# 05_DATA_IO.net
KiCad netlist of a schematic drawn in Altium Designer
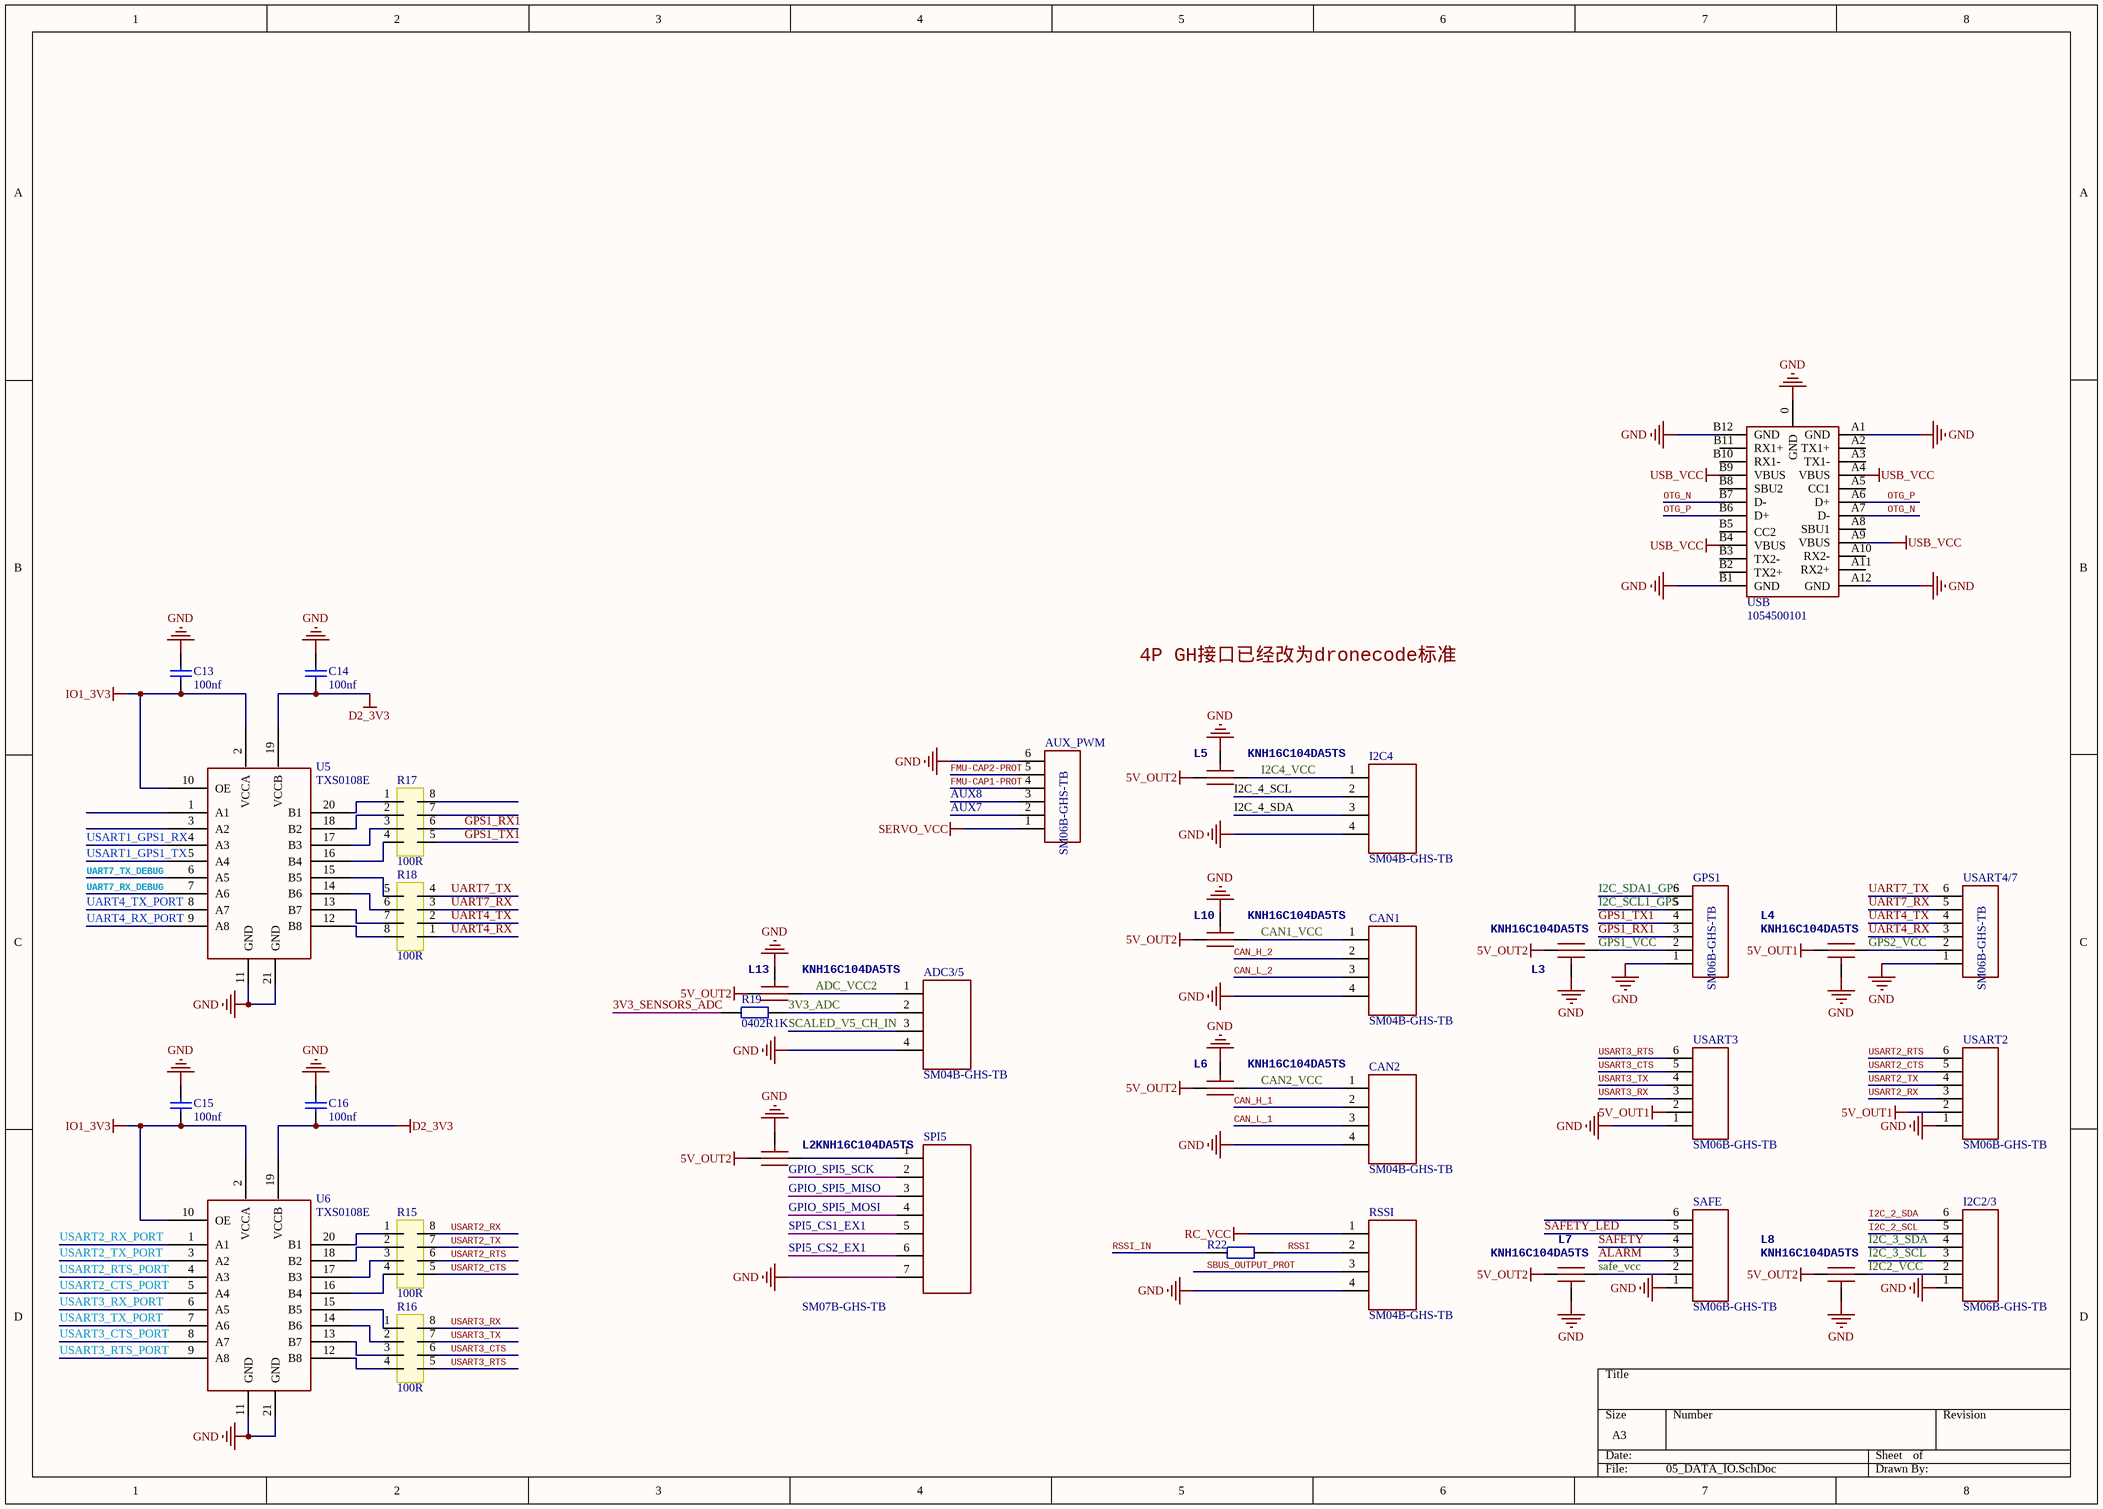
[diagram p0: 05_DATA_IO.SchDoc]

(export (version "E")
  (design (tool "Eeschema 10.0.6"))
  (components
    (comp (ref "ADC3/5")
      (value "SM04B-GHS-TB")
      (footprint "BM04B-GHS_DC")
      (libsource (lib "CUAV") (part "SM04B-GHS-TB"))
    )
    (comp (ref "AUX_PWM")
      (value "SM06B-GHS-TB")
      (footprint "BM06B-GHS_DC")
      (description "dronecode")
      (libsource (lib "CUAV") (part "SM06B-GHS-TB"))
    )
    (comp (ref "C13") (value "100nf") (libsource (lib "Miscellaneous Devices") (part "Cap")))
    (comp (ref "C14") (value "100nf") (libsource (lib "Miscellaneous Devices") (part "Cap")))
    (comp (ref "C15") (value "100nf") (libsource (lib "Miscellaneous Devices") (part "Cap")))
    (comp (ref "C16") (value "100nf") (libsource (lib "Miscellaneous Devices") (part "Cap")))
    (comp (ref "CAN1")
      (value "SM04B-GHS-TB")
      (footprint "BM04B-GHS_DC")
      (description "dronecode")
      (libsource (lib "CUAV") (part "SM04B-GHS-TB"))
    )
    (comp (ref "CAN2")
      (value "SM04B-GHS-TB")
      (footprint "BM04B-GHS_DC")
      (description "dronecode")
      (libsource (lib "CUAV") (part "SM04B-GHS-TB"))
    )
    (comp (ref "GPS1")
      (value "SM06B-GHS-TB")
      (footprint "SM06B-GHS-TB")
      (libsource (lib "CUAV") (part "SM06B-GHS-TB"))
    )
    (comp (ref "I2C2/3")
      (value "SM06B-GHS-TB")
      (footprint "SM06B-GHS-TB")
      (libsource (lib "CUAV") (part "SM06B-GHS-TB"))
    )
    (comp (ref "I2C4")
      (value "SM04B-GHS-TB")
      (footprint "BM04B-GHS_DC")
      (description "dronecode")
      (libsource (lib "CUAV") (part "SM04B-GHS-TB"))
    )
    (comp (ref "L2")
      (value "KNH16C104DA5TS")
      (footprint "KYOCERA-KNH16-DA")
      (description "Capacitor, Filter, 0.1uF, 25V, 2A, 0603, SMD")
      (fields (field (name "3DR_PARTNO") "ECM0719"))
      (libsource (lib "PCA_0005_FULL_CB_REV_A") (part "KNH16C104DA5TS"))
    )
    (comp (ref "L3")
      (value "KNH16C104DA5TS")
      (footprint "KYOCERA-KNH16-DA")
      (description "Capacitor, Filter, 0.1uF, 25V, 2A, 0603, SMD")
      (fields (field (name "3DR_PARTNO") "ECM0719"))
      (libsource (lib "PCA_0005_FULL_CB_REV_A") (part "KNH16C104DA5TS"))
    )
    (comp (ref "L4")
      (value "KNH16C104DA5TS")
      (footprint "KYOCERA-KNH16-DA")
      (description "Capacitor, Filter, 0.1uF, 25V, 2A, 0603, SMD")
      (fields (field (name "3DR_PARTNO") "ECM0719"))
      (libsource (lib "PCA_0005_FULL_CB_REV_A") (part "KNH16C104DA5TS"))
    )
    (comp (ref "L5")
      (value "KNH16C104DA5TS")
      (footprint "KYOCERA-KNH16-DA")
      (description "Capacitor, Filter, 0.1uF, 25V, 2A, 0603, SMD")
      (fields (field (name "3DR_PARTNO") "ECM0719"))
      (libsource (lib "PCA_0005_FULL_CB_REV_A") (part "KNH16C104DA5TS"))
    )
    (comp (ref "L6")
      (value "KNH16C104DA5TS")
      (footprint "KYOCERA-KNH16-DA")
      (description "Capacitor, Filter, 0.1uF, 25V, 2A, 0603, SMD")
      (fields (field (name "3DR_PARTNO") "ECM0719"))
      (libsource (lib "PCA_0005_FULL_CB_REV_A") (part "KNH16C104DA5TS"))
    )
    (comp (ref "L7")
      (value "KNH16C104DA5TS")
      (footprint "KYOCERA-KNH16-DA")
      (description "Capacitor, Filter, 0.1uF, 25V, 2A, 0603, SMD")
      (fields (field (name "3DR_PARTNO") "ECM0719"))
      (libsource (lib "PCA_0005_FULL_CB_REV_A") (part "KNH16C104DA5TS"))
    )
    (comp (ref "L8")
      (value "KNH16C104DA5TS")
      (footprint "KYOCERA-KNH16-DA")
      (description "Capacitor, Filter, 0.1uF, 25V, 2A, 0603, SMD")
      (fields (field (name "3DR_PARTNO") "ECM0719"))
      (libsource (lib "PCA_0005_FULL_CB_REV_A") (part "KNH16C104DA5TS"))
    )
    (comp (ref "L10")
      (value "KNH16C104DA5TS")
      (footprint "KYOCERA-KNH16-DA")
      (description "Capacitor, Filter, 0.1uF, 25V, 2A, 0603, SMD")
      (fields (field (name "3DR_PARTNO") "ECM0719"))
      (libsource (lib "PCA_0005_FULL_CB_REV_A") (part "KNH16C104DA5TS"))
    )
    (comp (ref "L13")
      (value "KNH16C104DA5TS")
      (footprint "KYOCERA-KNH16-DA")
      (description "Capacitor, Filter, 0.1uF, 25V, 2A, 0603, SMD")
      (fields (field (name "3DR_PARTNO") "ECM0719"))
      (libsource (lib "PCA_0005_FULL_CB_REV_A") (part "KNH16C104DA5TS"))
    )
    (comp (ref "R15") (value "100R") (footprint "0402_4r") (libsource (lib "") (part "0402-8R-4R_1")))
    (comp (ref "R16") (value "100R") (footprint "0402_4r") (libsource (lib "") (part "0402-8R-4R_1")))
    (comp (ref "R17") (value "100R") (footprint "0402_4r") (libsource (lib "") (part "0402-8R-4R_1")))
    (comp (ref "R18") (value "100R") (footprint "0402_4r") (libsource (lib "CUAV") (part "0402-8R-4R")))
    (comp (ref "R19")
      (value "0402R1K")
      (footprint "0402R")
      (description "0402R1K 1%")
      (libsource (lib "CUAV") (part "0402R1K"))
    )
    (comp (ref "R22")
      (value "0402R100R")
      (footprint "0402R")
      (description "0402R100R 1%")
      (libsource (lib "CUAV") (part "0402R100R"))
    )
    (comp (ref "RSSI")
      (value "SM04B-GHS-TB")
      (footprint "BM04B-GHS_DC")
      (description "dronecode")
      (libsource (lib "CUAV") (part "SM04B-GHS-TB"))
    )
    (comp (ref "SAFE")
      (value "SM06B-GHS-TB")
      (footprint "SM06B-GHS-TB")
      (libsource (lib "CUAV") (part "SM06B-GHS-TB"))
    )
    (comp (ref "SPI5")
      (value "SM07B-GHS-TB")
      (footprint "SM07B-GHS")
      (libsource (lib "CUAV") (part "SM07B-GHS-TB"))
    )
    (comp (ref "U5") (value "TXS0108E") (footprint "VQFN20") (libsource (lib "CUAV") (part "TXS0108E")))
    (comp (ref "U6") (value "TXS0108E") (footprint "VQFN20") (libsource (lib "CUAV") (part "TXS0108E")))
    (comp (ref "USART2")
      (value "SM06B-GHS-TB")
      (footprint "SM06B-GHS-TB")
      (libsource (lib "CUAV") (part "SM06B-GHS-TB"))
    )
    (comp (ref "USART3")
      (value "SM06B-GHS-TB")
      (footprint "SM06B-GHS-TB")
      (libsource (lib "CUAV") (part "SM06B-GHS-TB"))
    )
    (comp (ref "USART4/7")
      (value "SM06B-GHS-TB")
      (footprint "SM06B-GHS-TB")
      (libsource (lib "CUAV") (part "SM06B-GHS-TB"))
    )
    (comp (ref "USB")
      (value "1054500101")
      (footprint "1054500101")
      (libsource (lib "CUAV") (part "1054500101"))
    )
  )
  (nets
    (net (code "1") (name "/3V3_ADC") (class "Default")
      (node (ref "ADC3/5") (pin "2") (pintype "passive"))
      (node (ref "R19") (pin "2") (pintype "passive"))
    )
    (net (code "2") (name "/3V3_SENSORS_ADC") (class "Default")
      (node (ref "R19") (pin "1") (pintype "passive"))
    )
    (net (code "4") (name "/ADC_VCC2") (class "Default")
      (node (ref "ADC3/5") (pin "1") (pintype "passive"))
      (node (ref "L13") (pin "P$1") (pinfunction "P$1_P$1") (pintype "passive"))
    )
    (net (code "5") (name "/ALARM") (class "Default") (node (ref "SAFE") (pin "3") (pintype "passive")))
    (net (code "6") (name "/AUX7") (class "Default") (node (ref "AUX_PWM") (pin "2") (pintype "passive")))
    (net (code "7") (name "/AUX8") (class "Default") (node (ref "AUX_PWM") (pin "3") (pintype "passive")))
    (net (code "8") (name "/CAN1_VCC") (class "Default")
      (node (ref "CAN1") (pin "1") (pintype "passive"))
      (node (ref "L10") (pin "P$1") (pinfunction "P$1_P$1") (pintype "passive"))
    )
    (net (code "9") (name "/CAN2_VCC") (class "Default")
      (node (ref "CAN2") (pin "1") (pintype "passive"))
      (node (ref "L6") (pin "P$1") (pinfunction "P$1_P$1") (pintype "passive"))
    )
    (net (code "10") (name "/CAN_H_1") (class "Default") (node (ref "CAN2") (pin "2") (pintype "passive")))
    (net (code "11") (name "/CAN_H_2") (class "Default") (node (ref "CAN1") (pin "2") (pintype "passive")))
    (net (code "12") (name "/CAN_L_1") (class "Default") (node (ref "CAN2") (pin "3") (pintype "passive")))
    (net (code "13") (name "/CAN_L_2") (class "Default") (node (ref "CAN1") (pin "3") (pintype "passive")))
    (net (code "14") (name "/FMU-CAP1-PROT") (class "Default")
      (node (ref "AUX_PWM") (pin "4") (pintype "passive"))
    )
    (net (code "15") (name "/FMU-CAP2-PROT") (class "Default")
      (node (ref "AUX_PWM") (pin "5") (pintype "passive"))
    )
    (net (code "16") (name "/GPIO_SPI5_MISO") (class "Default")
      (node (ref "SPI5") (pin "3") (pintype "passive"))
    )
    (net (code "17") (name "/GPIO_SPI5_MOSI") (class "Default")
      (node (ref "SPI5") (pin "4") (pintype "passive"))
    )
    (net (code "18") (name "/GPIO_SPI5_SCK") (class "Default")
      (node (ref "SPI5") (pin "2") (pintype "passive"))
    )
    (net (code "19") (name "/GPS1_RX1") (class "Default")
      (node (ref "GPS1") (pin "3") (pintype "passive"))
      (node (ref "R17") (pin "6") (pinfunction "6_6") (pintype "passive"))
    )
    (net (code "20") (name "/GPS1_TX1") (class "Default")
      (node (ref "GPS1") (pin "4") (pintype "passive"))
      (node (ref "R17") (pin "5") (pinfunction "5_5") (pintype "passive"))
    )
    (net (code "21") (name "/GPS1_VCC") (class "Default")
      (node (ref "GPS1") (pin "2") (pintype "passive"))
      (node (ref "L3") (pin "P$2") (pinfunction "P$2_P$2") (pintype "passive"))
    )
    (net (code "22") (name "/GPS2_VCC") (class "Default")
      (node (ref "L4") (pin "P$2") (pinfunction "P$2_P$2") (pintype "passive"))
      (node (ref "USART4/7") (pin "2") (pintype "passive"))
    )
    (net (code "23") (name "/I2C2_VCC") (class "Default")
      (node (ref "I2C2/3") (pin "2") (pintype "passive"))
      (node (ref "L8") (pin "P$2") (pinfunction "P$2_P$2") (pintype "passive"))
    )
    (net (code "24") (name "/I2C4_VCC") (class "Default")
      (node (ref "I2C4") (pin "1") (pintype "passive"))
      (node (ref "L5") (pin "P$1") (pinfunction "P$1_P$1") (pintype "passive"))
    )
    (net (code "25") (name "/I2C_2_SCL") (class "Default")
      (node (ref "I2C2/3") (pin "5") (pintype "passive"))
    )
    (net (code "26") (name "/I2C_2_SDA") (class "Default")
      (node (ref "I2C2/3") (pin "6") (pintype "passive"))
    )
    (net (code "27") (name "/I2C_3_SCL") (class "Default")
      (node (ref "I2C2/3") (pin "3") (pintype "passive"))
    )
    (net (code "28") (name "/I2C_3_SDA") (class "Default")
      (node (ref "I2C2/3") (pin "4") (pintype "passive"))
    )
    (net (code "29") (name "/I2C_4_SCL") (class "Default") (node (ref "I2C4") (pin "2") (pintype "passive")))
    (net (code "30") (name "/I2C_4_SDA") (class "Default") (node (ref "I2C4") (pin "3") (pintype "passive")))
    (net (code "31") (name "/I2C_SCL1_GPS") (class "Default")
      (node (ref "GPS1") (pin "5") (pintype "passive"))
    )
    (net (code "32") (name "/I2C_SDA1_GPS") (class "Default")
      (node (ref "GPS1") (pin "6") (pintype "passive"))
    )
    (net (code "33") (name "/OTG_N") (class "Default")
      (node (ref "USB") (pin "A7") (pinfunction "D-_A7") (pintype "passive"))
      (node (ref "USB") (pin "B7") (pinfunction "D-_B7") (pintype "passive"))
    )
    (net (code "34") (name "/OTG_P") (class "Default")
      (node (ref "USB") (pin "A6") (pinfunction "D+_A6") (pintype "passive"))
      (node (ref "USB") (pin "B6") (pinfunction "D+_B6") (pintype "passive"))
    )
    (net (code "35") (name "/RSSI") (class "Default")
      (node (ref "R22") (pin "2") (pintype "passive"))
      (node (ref "RSSI") (pin "2") (pintype "passive"))
    )
    (net (code "36") (name "/RSSI_IN") (class "Default") (node (ref "R22") (pin "1") (pintype "passive")))
    (net (code "37") (name "/SAFETY") (class "Default") (node (ref "SAFE") (pin "4") (pintype "passive")))
    (net (code "38") (name "/SAFETY_LED") (class "Default") (node (ref "SAFE") (pin "5") (pintype "passive")))
    (net (code "39") (name "/SBUS_OUTPUT_PROT") (class "Default")
      (node (ref "RSSI") (pin "3") (pintype "passive"))
    )
    (net (code "40") (name "/SCALED_V5_CH_IN") (class "Default")
      (node (ref "ADC3/5") (pin "3") (pintype "passive"))
    )
    (net (code "41") (name "/SPI5_CS1_EX1") (class "Default")
      (node (ref "SPI5") (pin "5") (pintype "passive"))
    )
    (net (code "42") (name "/SPI5_CS2_EX1") (class "Default")
      (node (ref "SPI5") (pin "6") (pintype "passive"))
    )
    (net (code "43") (name "/UART4_RX") (class "Default")
      (node (ref "R18") (pin "1") (pinfunction "1_1") (pintype "passive"))
      (node (ref "USART4/7") (pin "3") (pintype "passive"))
    )
    (net (code "44") (name "/UART4_RX_PORT") (class "Default")
      (node (ref "U5") (pin "9") (pinfunction "A8_9") (pintype "passive"))
    )
    (net (code "45") (name "/UART4_TX") (class "Default")
      (node (ref "R18") (pin "2") (pinfunction "2_2") (pintype "passive"))
      (node (ref "USART4/7") (pin "4") (pintype "passive"))
    )
    (net (code "46") (name "/UART4_TX_PORT") (class "Default")
      (node (ref "U5") (pin "8") (pinfunction "A7_8") (pintype "passive"))
    )
    (net (code "47") (name "/UART7_RX") (class "Default")
      (node (ref "R18") (pin "3") (pinfunction "3_3") (pintype "passive"))
      (node (ref "USART4/7") (pin "5") (pintype "passive"))
    )
    (net (code "48") (name "/UART7_RX_DEBUG") (class "Default")
      (node (ref "U5") (pin "7") (pinfunction "A6_7") (pintype "passive"))
    )
    (net (code "49") (name "/UART7_TX") (class "Default")
      (node (ref "R18") (pin "4") (pinfunction "4_4") (pintype "passive"))
      (node (ref "USART4/7") (pin "6") (pintype "passive"))
    )
    (net (code "50") (name "/UART7_TX_DEBUG") (class "Default")
      (node (ref "U5") (pin "6") (pinfunction "A5_6") (pintype "passive"))
    )
    (net (code "51") (name "/USART1_GPS1_RX") (class "Default")
      (node (ref "U5") (pin "4") (pinfunction "A3_4") (pintype "passive"))
    )
    (net (code "52") (name "/USART1_GPS1_TX") (class "Default")
      (node (ref "U5") (pin "5") (pinfunction "A4_5") (pintype "passive"))
    )
    (net (code "53") (name "/USART2_CTS") (class "Default")
      (node (ref "R15") (pin "5") (pinfunction "5_5") (pintype "passive"))
      (node (ref "USART2") (pin "5") (pintype "passive"))
    )
    (net (code "54") (name "/USART2_CTS_PORT") (class "Default")
      (node (ref "U6") (pin "5") (pinfunction "A4_5") (pintype "passive"))
    )
    (net (code "55") (name "/USART2_RTS") (class "Default")
      (node (ref "R15") (pin "6") (pinfunction "6_6") (pintype "passive"))
      (node (ref "USART2") (pin "6") (pintype "passive"))
    )
    (net (code "56") (name "/USART2_RTS_PORT") (class "Default")
      (node (ref "U6") (pin "4") (pinfunction "A3_4") (pintype "passive"))
    )
    (net (code "57") (name "/USART2_RX") (class "Default")
      (node (ref "R15") (pin "8") (pinfunction "8_8") (pintype "passive"))
      (node (ref "USART2") (pin "3") (pintype "passive"))
    )
    (net (code "58") (name "/USART2_RX_PORT") (class "Default")
      (node (ref "U6") (pin "1") (pinfunction "A1_1") (pintype "passive"))
    )
    (net (code "59") (name "/USART2_TX") (class "Default")
      (node (ref "R15") (pin "7") (pinfunction "7_7") (pintype "passive"))
      (node (ref "USART2") (pin "4") (pintype "passive"))
    )
    (net (code "60") (name "/USART2_TX_PORT") (class "Default")
      (node (ref "U6") (pin "3") (pinfunction "A2_3") (pintype "passive"))
    )
    (net (code "61") (name "/USART3_CTS") (class "Default")
      (node (ref "R16") (pin "6") (pinfunction "6_6") (pintype "passive"))
      (node (ref "USART3") (pin "5") (pintype "passive"))
    )
    (net (code "62") (name "/USART3_CTS_PORT") (class "Default")
      (node (ref "U6") (pin "8") (pinfunction "A7_8") (pintype "passive"))
    )
    (net (code "63") (name "/USART3_RTS") (class "Default")
      (node (ref "R16") (pin "5") (pinfunction "5_5") (pintype "passive"))
      (node (ref "USART3") (pin "6") (pintype "passive"))
    )
    (net (code "64") (name "/USART3_RTS_PORT") (class "Default")
      (node (ref "U6") (pin "9") (pinfunction "A8_9") (pintype "passive"))
    )
    (net (code "65") (name "/USART3_RX") (class "Default")
      (node (ref "R16") (pin "8") (pinfunction "8_8") (pintype "passive"))
      (node (ref "USART3") (pin "3") (pintype "passive"))
    )
    (net (code "66") (name "/USART3_RX_PORT") (class "Default")
      (node (ref "U6") (pin "6") (pinfunction "A5_6") (pintype "passive"))
    )
    (net (code "67") (name "/USART3_TX") (class "Default")
      (node (ref "R16") (pin "7") (pinfunction "7_7") (pintype "passive"))
      (node (ref "USART3") (pin "4") (pintype "passive"))
    )
    (net (code "68") (name "/USART3_TX_PORT") (class "Default")
      (node (ref "U6") (pin "7") (pinfunction "A6_7") (pintype "passive"))
    )
    (net (code "69") (name "/safe_vcc") (class "Default")
      (node (ref "L7") (pin "P$2") (pinfunction "P$2_P$2") (pintype "passive"))
      (node (ref "SAFE") (pin "2") (pintype "passive"))
    )
    (net (code "70") (name "5V_OUT1") (class "Default")
      (node (ref "L4") (pin "P$1") (pinfunction "P$1_P$1") (pintype "passive"))
      (node (ref "USART2") (pin "2") (pintype "passive"))
      (node (ref "USART3") (pin "2") (pintype "passive"))
    )
    (net (code "71") (name "5V_OUT2") (class "Default")
      (node (ref "L10") (pin "P$2") (pinfunction "P$2_P$2") (pintype "passive"))
      (node (ref "L13") (pin "P$2") (pinfunction "P$2_P$2") (pintype "passive"))
      (node (ref "L2") (pin "P$2") (pinfunction "P$2_P$2") (pintype "passive"))
      (node (ref "L3") (pin "P$1") (pinfunction "P$1_P$1") (pintype "passive"))
      (node (ref "L5") (pin "P$2") (pinfunction "P$2_P$2") (pintype "passive"))
      (node (ref "L6") (pin "P$2") (pinfunction "P$2_P$2") (pintype "passive"))
      (node (ref "L7") (pin "P$1") (pinfunction "P$1_P$1") (pintype "passive"))
      (node (ref "L8") (pin "P$1") (pinfunction "P$1_P$1") (pintype "passive"))
    )
    (net (code "72") (name "D2_3V3") (class "Default")
      (node (ref "C14") (pin "2") (pinfunction "2_2") (pintype "passive"))
      (node (ref "C16") (pin "2") (pinfunction "2_2") (pintype "passive"))
      (node (ref "U5") (pin "19") (pinfunction "VCCB_19") (pintype "passive"))
      (node (ref "U6") (pin "19") (pinfunction "VCCB_19") (pintype "passive"))
    )
    (net (code "73") (name "GND") (class "Default")
      (node (ref "ADC3/5") (pin "4") (pintype "passive"))
      (node (ref "AUX_PWM") (pin "6") (pintype "passive"))
      (node (ref "C13") (pin "1") (pinfunction "1_1") (pintype "passive"))
      (node (ref "C14") (pin "1") (pinfunction "1_1") (pintype "passive"))
      (node (ref "C15") (pin "1") (pinfunction "1_1") (pintype "passive"))
      (node (ref "C16") (pin "1") (pinfunction "1_1") (pintype "passive"))
      (node (ref "CAN1") (pin "4") (pintype "passive"))
      (node (ref "CAN2") (pin "4") (pintype "passive"))
      (node (ref "GPS1") (pin "1") (pintype "passive"))
      (node (ref "I2C2/3") (pin "1") (pintype "passive"))
      (node (ref "I2C4") (pin "4") (pintype "passive"))
      (node (ref "L10") (pin "GND") (pinfunction "GND_GND") (pintype "passive"))
      (node (ref "L13") (pin "GND") (pinfunction "GND_GND") (pintype "passive"))
      (node (ref "L2") (pin "GND") (pinfunction "GND_GND") (pintype "passive"))
      (node (ref "L3") (pin "GND") (pinfunction "GND_GND") (pintype "passive"))
      (node (ref "L4") (pin "GND") (pinfunction "GND_GND") (pintype "passive"))
      (node (ref "L5") (pin "GND") (pinfunction "GND_GND") (pintype "passive"))
      (node (ref "L6") (pin "GND") (pinfunction "GND_GND") (pintype "passive"))
      (node (ref "L7") (pin "GND") (pinfunction "GND_GND") (pintype "passive"))
      (node (ref "L8") (pin "GND") (pinfunction "GND_GND") (pintype "passive"))
      (node (ref "RSSI") (pin "4") (pintype "passive"))
      (node (ref "SAFE") (pin "1") (pintype "passive"))
      (node (ref "SPI5") (pin "7") (pintype "passive"))
      (node (ref "U5") (pin "11") (pinfunction "GND_11") (pintype "passive"))
      (node (ref "U5") (pin "21") (pinfunction "GND_21") (pintype "passive"))
      (node (ref "U6") (pin "11") (pinfunction "GND_11") (pintype "passive"))
      (node (ref "U6") (pin "21") (pinfunction "GND_21") (pintype "passive"))
      (node (ref "USART2") (pin "1") (pintype "passive"))
      (node (ref "USART3") (pin "1") (pintype "passive"))
      (node (ref "USART4/7") (pin "1") (pintype "passive"))
      (node (ref "USB") (pin "0") (pinfunction "GND_0") (pintype "passive"))
      (node (ref "USB") (pin "A1") (pinfunction "GND_A1") (pintype "passive"))
      (node (ref "USB") (pin "A12") (pinfunction "GND_A12") (pintype "passive"))
      (node (ref "USB") (pin "B1") (pinfunction "GND_B1") (pintype "passive"))
      (node (ref "USB") (pin "B12") (pinfunction "GND_B12") (pintype "passive"))
    )
    (net (code "74") (name "IO1_3V3") (class "Default")
      (node (ref "C13") (pin "2") (pinfunction "2_2") (pintype "passive"))
      (node (ref "C15") (pin "2") (pinfunction "2_2") (pintype "passive"))
      (node (ref "U5") (pin "10") (pinfunction "OE_10") (pintype "passive"))
      (node (ref "U5") (pin "2") (pinfunction "VCCA_2") (pintype "passive"))
      (node (ref "U6") (pin "10") (pinfunction "OE_10") (pintype "passive"))
      (node (ref "U6") (pin "2") (pinfunction "VCCA_2") (pintype "passive"))
    )
    (net (code "75") (name "Net-(L2-PadP$1)") (class "Default")
      (node (ref "L2") (pin "P$1") (pinfunction "P$1_P$1") (pintype "passive"))
      (node (ref "SPI5") (pin "1") (pintype "passive"))
    )
    (net (code "76") (name "Net-(U5-B1)") (class "Default")
      (node (ref "R17") (pin "1") (pinfunction "1_1") (pintype "passive"))
      (node (ref "U5") (pin "20") (pinfunction "B1_20") (pintype "passive"))
    )
    (net (code "77") (name "Net-(U5-B2)") (class "Default")
      (node (ref "R17") (pin "2") (pinfunction "2_2") (pintype "passive"))
      (node (ref "U5") (pin "18") (pinfunction "B2_18") (pintype "passive"))
    )
    (net (code "78") (name "Net-(U5-B3)") (class "Default")
      (node (ref "R17") (pin "3") (pinfunction "3_3") (pintype "passive"))
      (node (ref "U5") (pin "17") (pinfunction "B3_17") (pintype "passive"))
    )
    (net (code "79") (name "Net-(U5-B4)") (class "Default")
      (node (ref "R17") (pin "4") (pinfunction "4_4") (pintype "passive"))
      (node (ref "U5") (pin "16") (pinfunction "B4_16") (pintype "passive"))
    )
    (net (code "80") (name "Net-(U5-B5)") (class "Default")
      (node (ref "R18") (pin "5") (pinfunction "5_5") (pintype "passive"))
      (node (ref "U5") (pin "15") (pinfunction "B5_15") (pintype "passive"))
    )
    (net (code "81") (name "Net-(U5-B6)") (class "Default")
      (node (ref "R18") (pin "6") (pinfunction "6_6") (pintype "passive"))
      (node (ref "U5") (pin "14") (pinfunction "B6_14") (pintype "passive"))
    )
    (net (code "82") (name "Net-(U5-B7)") (class "Default")
      (node (ref "R18") (pin "7") (pinfunction "7_7") (pintype "passive"))
      (node (ref "U5") (pin "13") (pinfunction "B7_13") (pintype "passive"))
    )
    (net (code "83") (name "Net-(U5-B8)") (class "Default")
      (node (ref "R18") (pin "8") (pinfunction "8_8") (pintype "passive"))
      (node (ref "U5") (pin "12") (pinfunction "B8_12") (pintype "passive"))
    )
    (net (code "84") (name "Net-(U6-B1)") (class "Default")
      (node (ref "R15") (pin "1") (pinfunction "1_1") (pintype "passive"))
      (node (ref "U6") (pin "20") (pinfunction "B1_20") (pintype "passive"))
    )
    (net (code "85") (name "Net-(U6-B2)") (class "Default")
      (node (ref "R15") (pin "2") (pinfunction "2_2") (pintype "passive"))
      (node (ref "U6") (pin "18") (pinfunction "B2_18") (pintype "passive"))
    )
    (net (code "86") (name "Net-(U6-B3)") (class "Default")
      (node (ref "R15") (pin "3") (pinfunction "3_3") (pintype "passive"))
      (node (ref "U6") (pin "17") (pinfunction "B3_17") (pintype "passive"))
    )
    (net (code "87") (name "Net-(U6-B4)") (class "Default")
      (node (ref "R15") (pin "4") (pinfunction "4_4") (pintype "passive"))
      (node (ref "U6") (pin "16") (pinfunction "B4_16") (pintype "passive"))
    )
    (net (code "88") (name "Net-(U6-B5)") (class "Default")
      (node (ref "R16") (pin "1") (pinfunction "1_1") (pintype "passive"))
      (node (ref "U6") (pin "15") (pinfunction "B5_15") (pintype "passive"))
    )
    (net (code "89") (name "Net-(U6-B6)") (class "Default")
      (node (ref "R16") (pin "2") (pinfunction "2_2") (pintype "passive"))
      (node (ref "U6") (pin "14") (pinfunction "B6_14") (pintype "passive"))
    )
    (net (code "90") (name "Net-(U6-B7)") (class "Default")
      (node (ref "R16") (pin "3") (pinfunction "3_3") (pintype "passive"))
      (node (ref "U6") (pin "13") (pinfunction "B7_13") (pintype "passive"))
    )
    (net (code "91") (name "Net-(U6-B8)") (class "Default")
      (node (ref "R16") (pin "4") (pinfunction "4_4") (pintype "passive"))
      (node (ref "U6") (pin "12") (pinfunction "B8_12") (pintype "passive"))
    )
    (net (code "92") (name "RC_VCC") (class "Default") (node (ref "RSSI") (pin "1") (pintype "passive")))
    (net (code "93") (name "SERVO_VCC") (class "Default")
      (node (ref "AUX_PWM") (pin "1") (pintype "passive"))
    )
    (net (code "94") (name "USB_VCC") (class "Default")
      (node (ref "USB") (pin "A4") (pinfunction "VBUS_A4") (pintype "passive"))
      (node (ref "USB") (pin "A9") (pinfunction "VBUS_A9") (pintype "passive"))
      (node (ref "USB") (pin "B4") (pinfunction "VBUS_B4") (pintype "passive"))
      (node (ref "USB") (pin "B9") (pinfunction "VBUS_B9") (pintype "passive"))
    )
    (net (code "95") (name "unconnected-(R17-Pad7)") (class "Default")
      (node (ref "R17") (pin "7") (pinfunction "7_7") (pintype "passive"))
    )
    (net (code "96") (name "unconnected-(R17-Pad8)") (class "Default")
      (node (ref "R17") (pin "8") (pinfunction "8_8") (pintype "passive"))
    )
    (net (code "97") (name "unconnected-(SAFE-Pad6)") (class "Default")
      (node (ref "SAFE") (pin "6") (pintype "passive"))
    )
    (net (code "98") (name "unconnected-(U5-A1-Pad1)") (class "Default")
      (node (ref "U5") (pin "1") (pinfunction "A1_1") (pintype "passive"))
    )
    (net (code "99") (name "unconnected-(U5-A2-Pad3)") (class "Default")
      (node (ref "U5") (pin "3") (pinfunction "A2_3") (pintype "passive"))
    )
    (net (code "100") (name "unconnected-(USB-CC1-PadA5)") (class "Default")
      (node (ref "USB") (pin "A5") (pinfunction "CC1_A5") (pintype "passive"))
    )
    (net (code "101") (name "unconnected-(USB-CC2-PadB5)") (class "Default")
      (node (ref "USB") (pin "B5") (pinfunction "CC2_B5") (pintype "passive"))
    )
    (net (code "102") (name "unconnected-(USB-RX1+-PadB11)") (class "Default")
      (node (ref "USB") (pin "B11") (pinfunction "RX1+_B11") (pintype "passive"))
    )
    (net (code "103") (name "unconnected-(USB-RX1--PadB10)") (class "Default")
      (node (ref "USB") (pin "B10") (pinfunction "RX1-_B10") (pintype "passive"))
    )
    (net (code "104") (name "unconnected-(USB-RX2+-PadA11)") (class "Default")
      (node (ref "USB") (pin "A11") (pinfunction "RX2+_A11") (pintype "passive"))
    )
    (net (code "105") (name "unconnected-(USB-RX2--PadA10)") (class "Default")
      (node (ref "USB") (pin "A10") (pinfunction "RX2-_A10") (pintype "passive"))
    )
    (net (code "106") (name "unconnected-(USB-SBU1-PadA8)") (class "Default")
      (node (ref "USB") (pin "A8") (pinfunction "SBU1_A8") (pintype "passive"))
    )
    (net (code "107") (name "unconnected-(USB-SBU2-PadB8)") (class "Default")
      (node (ref "USB") (pin "B8") (pinfunction "SBU2_B8") (pintype "passive"))
    )
    (net (code "108") (name "unconnected-(USB-TX1+-PadA2)") (class "Default")
      (node (ref "USB") (pin "A2") (pinfunction "TX1+_A2") (pintype "passive"))
    )
    (net (code "109") (name "unconnected-(USB-TX1--PadA3)") (class "Default")
      (node (ref "USB") (pin "A3") (pinfunction "TX1-_A3") (pintype "passive"))
    )
    (net (code "110") (name "unconnected-(USB-TX2+-PadB2)") (class "Default")
      (node (ref "USB") (pin "B2") (pinfunction "TX2+_B2") (pintype "passive"))
    )
    (net (code "111") (name "unconnected-(USB-TX2--PadB3)") (class "Default")
      (node (ref "USB") (pin "B3") (pinfunction "TX2-_B3") (pintype "passive"))
    )
  )
)
